# v1_0.net
KiCad netlist of a schematic drawn in Altium Designer
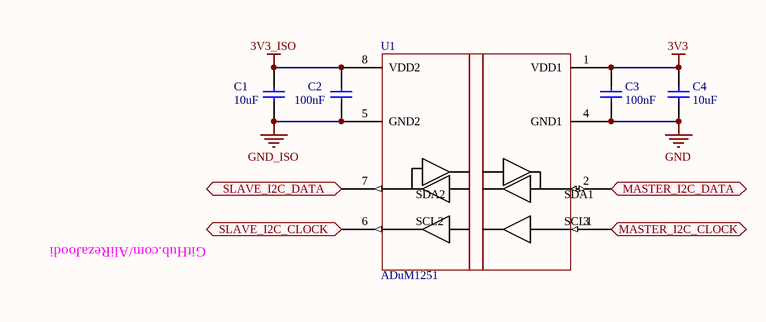
[diagram p0: v1.0.SchDoc]

(export (version "E")
  (design (tool "Eeschema 10.0.6"))
  (components
    (comp (ref "C1")
      (value "10uF")
      (footprint "Capacitor_Ceramic:SMD_0805")
      (description "Capacitor, Ceramic Multilayer")
      (libsource (lib "General") (part "Capacitor_Ceramic"))
    )
    (comp (ref "C2")
      (value "100nF")
      (footprint "Capacitor_Ceramic:SMD_0805")
      (description "Capacitor, Ceramic Multilayer")
      (libsource (lib "General") (part "Capacitor_Ceramic"))
    )
    (comp (ref "C3")
      (value "100nF")
      (footprint "Capacitor_Ceramic:SMD_0805")
      (description "Capacitor, Ceramic Multilayer")
      (libsource (lib "General") (part "Capacitor_Ceramic"))
    )
    (comp (ref "C4")
      (value "10uF")
      (footprint "Capacitor_Ceramic:SMD_0805")
      (description "Capacitor, Ceramic Multilayer")
      (libsource (lib "General") (part "Capacitor_Ceramic"))
    )
    (comp (ref "U1")
      (value "ADuM1251")
      (description "IC, Isolated I2C")
      (fields (field (name "1_PART NUMBER") "ADUM1251ARZ"))
      (libsource (lib "IC") (part "Isolator_ADuM1251"))
    )
  )
  (nets
    (net (code "1") (name "/MASTER_I2C_CLOCK") (class "Default")
      (node (ref "U1") (pin "3") (pinfunction "SCL1_3") (pintype "input"))
    )
    (net (code "2") (name "/MASTER_I2C_DATA") (class "Default")
      (node (ref "U1") (pin "2") (pinfunction "SDA1_2") (pintype "bidirectional"))
    )
    (net (code "3") (name "/SLAVE_I2C_CLOCK") (class "Default")
      (node (ref "U1") (pin "6") (pinfunction "SCL2_6") (pintype "output"))
    )
    (net (code "4") (name "/SLAVE_I2C_DATA") (class "Default")
      (node (ref "U1") (pin "7") (pinfunction "SDA2_7") (pintype "output"))
    )
    (net (code "5") (name "3V3") (class "Default")
      (node (ref "C3") (pin "2") (pinfunction "2_2") (pintype "passive"))
      (node (ref "C4") (pin "1") (pinfunction "1_1") (pintype "passive"))
      (node (ref "U1") (pin "1") (pinfunction "VDD1_1") (pintype "passive"))
    )
    (net (code "6") (name "3V3_ISO") (class "Default")
      (node (ref "C1") (pin "1") (pinfunction "1_1") (pintype "passive"))
      (node (ref "C2") (pin "2") (pinfunction "2_2") (pintype "passive"))
      (node (ref "U1") (pin "8") (pinfunction "VDD2_8") (pintype "passive"))
    )
    (net (code "7") (name "GND") (class "Default")
      (node (ref "C3") (pin "1") (pinfunction "1_1") (pintype "passive"))
      (node (ref "C4") (pin "2") (pinfunction "2_2") (pintype "passive"))
      (node (ref "U1") (pin "4") (pinfunction "GND1_4") (pintype "passive"))
    )
    (net (code "8") (name "GND_ISO") (class "Default")
      (node (ref "C1") (pin "2") (pinfunction "2_2") (pintype "passive"))
      (node (ref "C2") (pin "1") (pinfunction "1_1") (pintype "passive"))
      (node (ref "U1") (pin "5") (pinfunction "GND2_5") (pintype "passive"))
    )
  )
)
